# Pressure_Transducers_SCH.net
KiCad netlist of a schematic drawn in Altium Designer
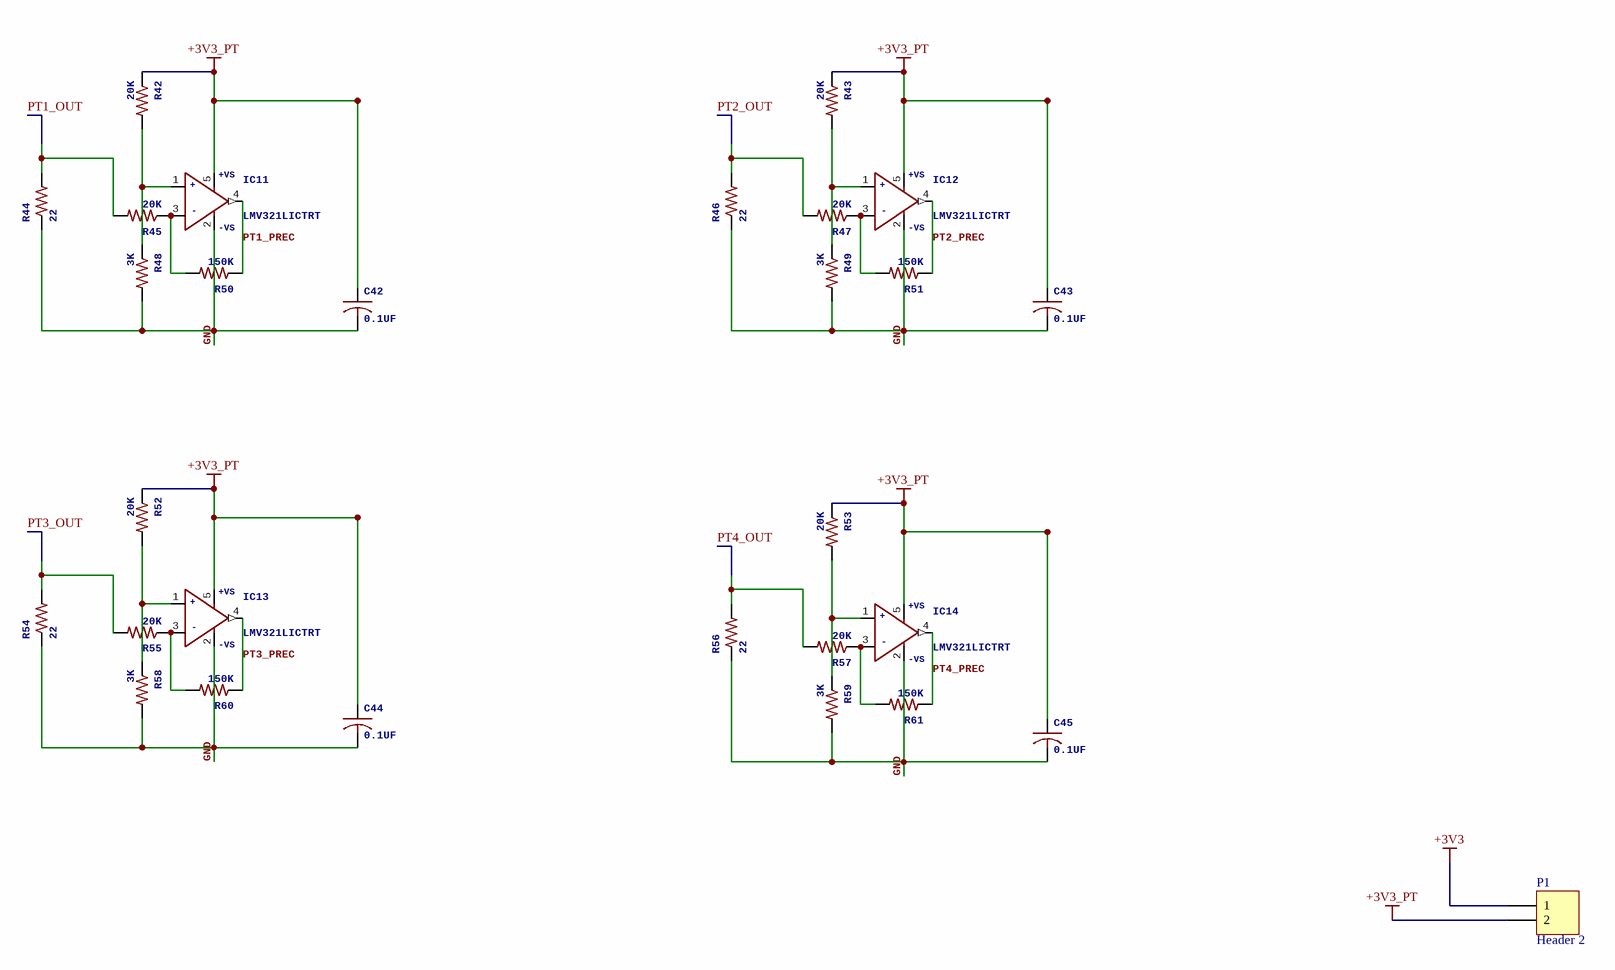
[diagram p0: Pressure_Transducers_SCH.SchDoc]

(export (version "E")
  (design (tool "Eeschema 10.0.6"))
  (components
    (comp (ref "C42")
      (value "0.1UF")
      (footprint "CAPCP2012X06N")
      (description "CAPACITOR, American symbol")
      (libsource (lib "rcl") (part "C-USC0805"))
    )
    (comp (ref "C43")
      (value "0.1UF")
      (footprint "CAPCP2012X06N")
      (description "CAPACITOR, American symbol")
      (libsource (lib "rcl") (part "C-USC0805"))
    )
    (comp (ref "C44")
      (value "0.1UF")
      (footprint "CAPCP2012X06N")
      (description "CAPACITOR, American symbol")
      (libsource (lib "rcl") (part "C-USC0805"))
    )
    (comp (ref "C45")
      (value "0.1UF")
      (footprint "CAPCP2012X06N")
      (description "CAPACITOR, American symbol")
      (libsource (lib "rcl") (part "C-USC0805"))
    )
    (comp (ref "IC11")
      (value "LMV321LICTRT")
      (footprint "SOT95P245X110-5N")
      (fields
        (field (name "MF") "ALTERA CORPORATION")
        (field (name "MPN") "AD8065ARTZ-REEL7")
        (field (name "+") "+")
        (field (name "-") "-")
        (field (name "+VS") "+VS")
        (field (name "-VS") "-VS")
        (field (name "LIBRARYNAME") "st-microelectronics-extra")
      )
      (libsource (lib "st-microelectronics-extra") (part "LMV321LICTRT"))
    )
    (comp (ref "IC12")
      (value "LMV321LICTRT")
      (footprint "SOT95P245X110-5N")
      (fields
        (field (name "MF") "ALTERA CORPORATION")
        (field (name "MPN") "AD8065ARTZ-REEL7")
        (field (name "+") "+")
        (field (name "-") "-")
        (field (name "+VS") "+VS")
        (field (name "-VS") "-VS")
        (field (name "LIBRARYNAME") "st-microelectronics-extra")
      )
      (libsource (lib "st-microelectronics-extra") (part "LMV321LICTRT"))
    )
    (comp (ref "IC13")
      (value "LMV321LICTRT")
      (footprint "SOT95P245X110-5N")
      (fields
        (field (name "MF") "ALTERA CORPORATION")
        (field (name "MPN") "AD8065ARTZ-REEL7")
        (field (name "+") "+")
        (field (name "-") "-")
        (field (name "+VS") "+VS")
        (field (name "-VS") "-VS")
        (field (name "LIBRARYNAME") "st-microelectronics-extra")
      )
      (libsource (lib "st-microelectronics-extra") (part "LMV321LICTRT"))
    )
    (comp (ref "IC14")
      (value "LMV321LICTRT")
      (footprint "SOT95P245X110-5N")
      (fields
        (field (name "MF") "ALTERA CORPORATION")
        (field (name "MPN") "AD8065ARTZ-REEL7")
        (field (name "+") "+")
        (field (name "-") "-")
        (field (name "+VS") "+VS")
        (field (name "-VS") "-VS")
        (field (name "LIBRARYNAME") "st-microelectronics-extra")
      )
      (libsource (lib "st-microelectronics-extra") (part "LMV321LICTRT"))
    )
    (comp (ref "P1")
      (value "Header 2")
      (footprint "HDR1X2")
      (description "Header, 2-Pin")
      (fields (field (name "PUBLISHER") "Altium Limited"))
      (libsource (lib "Miscellaneous Connectors") (part "Header 2"))
    )
    (comp (ref "R42")
      (value "20K")
      (footprint "RESC_0805_2012")
      (description "RESISTOR, American symbol")
      (libsource (lib "rcl") (part "R-US_R0805"))
    )
    (comp (ref "R43")
      (value "20K")
      (footprint "RESC_0805_2012")
      (description "RESISTOR, American symbol")
      (libsource (lib "rcl") (part "R-US_R0805"))
    )
    (comp (ref "R44")
      (value "22")
      (footprint "RESC_0805_2012")
      (description "RESISTOR, American symbol")
      (libsource (lib "rcl") (part "R-US_R0805"))
    )
    (comp (ref "R45")
      (value "20K")
      (footprint "RESC_0805_2012")
      (description "RESISTOR, American symbol")
      (libsource (lib "rcl") (part "R-US_R0805"))
    )
    (comp (ref "R46")
      (value "22")
      (footprint "RESC_0805_2012")
      (description "RESISTOR, American symbol")
      (libsource (lib "rcl") (part "R-US_R0805"))
    )
    (comp (ref "R47")
      (value "20K")
      (footprint "RESC_0805_2012")
      (description "RESISTOR, American symbol")
      (libsource (lib "rcl") (part "R-US_R0805"))
    )
    (comp (ref "R48")
      (value "3K")
      (footprint "RESC_0805_2012")
      (description "RESISTOR, American symbol")
      (libsource (lib "rcl") (part "R-US_R0805"))
    )
    (comp (ref "R49")
      (value "3K")
      (footprint "RESC_0805_2012")
      (description "RESISTOR, American symbol")
      (libsource (lib "rcl") (part "R-US_R0805"))
    )
    (comp (ref "R50")
      (value "150K")
      (footprint "RESC_0805_2012")
      (description "RESISTOR, American symbol")
      (libsource (lib "rcl") (part "R-US_R0805"))
    )
    (comp (ref "R51")
      (value "150K")
      (footprint "RESC_0805_2012")
      (description "RESISTOR, American symbol")
      (libsource (lib "rcl") (part "R-US_R0805"))
    )
    (comp (ref "R52")
      (value "20K")
      (footprint "RESC_0805_2012")
      (description "RESISTOR, American symbol")
      (libsource (lib "rcl") (part "R-US_R0805"))
    )
    (comp (ref "R53")
      (value "20K")
      (footprint "RESC_0805_2012")
      (description "RESISTOR, American symbol")
      (libsource (lib "rcl") (part "R-US_R0805"))
    )
    (comp (ref "R54")
      (value "22")
      (footprint "RESC_0805_2012")
      (description "RESISTOR, American symbol")
      (libsource (lib "rcl") (part "R-US_R0805"))
    )
    (comp (ref "R55")
      (value "20K")
      (footprint "RESC_0805_2012")
      (description "RESISTOR, American symbol")
      (libsource (lib "rcl") (part "R-US_R0805"))
    )
    (comp (ref "R56")
      (value "22")
      (footprint "RESC_0805_2012")
      (description "RESISTOR, American symbol")
      (libsource (lib "rcl") (part "R-US_R0805"))
    )
    (comp (ref "R57")
      (value "20K")
      (footprint "RESC_0805_2012")
      (description "RESISTOR, American symbol")
      (libsource (lib "rcl") (part "R-US_R0805"))
    )
    (comp (ref "R58")
      (value "3K")
      (footprint "RESC_0805_2012")
      (description "RESISTOR, American symbol")
      (libsource (lib "rcl") (part "R-US_R0805"))
    )
    (comp (ref "R59")
      (value "3K")
      (footprint "RESC_0805_2012")
      (description "RESISTOR, American symbol")
      (libsource (lib "rcl") (part "R-US_R0805"))
    )
    (comp (ref "R60")
      (value "150K")
      (footprint "RESC_0805_2012")
      (description "RESISTOR, American symbol")
      (libsource (lib "rcl") (part "R-US_R0805"))
    )
    (comp (ref "R61")
      (value "150K")
      (footprint "RESC_0805_2012")
      (description "RESISTOR, American symbol")
      (libsource (lib "rcl") (part "R-US_R0805"))
    )
  )
  (nets
    (net (code "1") (name "+3V3") (class "Default")
      (node (ref "P1") (pin "1") (pinfunction "1_1") (pintype "passive"))
    )
    (net (code "2") (name "+3V3_PT") (class "Default")
      (node (ref "C42") (pin "1") (pinfunction "1_1") (pintype "passive"))
      (node (ref "C43") (pin "1") (pinfunction "1_1") (pintype "passive"))
      (node (ref "C44") (pin "1") (pinfunction "1_1") (pintype "passive"))
      (node (ref "C45") (pin "1") (pinfunction "1_1") (pintype "passive"))
      (node (ref "IC11") (pin "5") (pinfunction "+VS_5") (pintype "passive"))
      (node (ref "IC12") (pin "5") (pinfunction "+VS_5") (pintype "passive"))
      (node (ref "IC13") (pin "5") (pinfunction "+VS_5") (pintype "passive"))
      (node (ref "IC14") (pin "5") (pinfunction "+VS_5") (pintype "passive"))
      (node (ref "P1") (pin "2") (pinfunction "2_2") (pintype "passive"))
      (node (ref "R42") (pin "1") (pinfunction "1_1") (pintype "passive"))
      (node (ref "R43") (pin "1") (pinfunction "1_1") (pintype "passive"))
      (node (ref "R52") (pin "1") (pinfunction "1_1") (pintype "passive"))
      (node (ref "R53") (pin "1") (pinfunction "1_1") (pintype "passive"))
    )
    (net (code "3") (name "/GND") (class "Default")
      (node (ref "C42") (pin "2") (pinfunction "2_2") (pintype "passive"))
      (node (ref "C43") (pin "2") (pinfunction "2_2") (pintype "passive"))
      (node (ref "C44") (pin "2") (pinfunction "2_2") (pintype "passive"))
      (node (ref "C45") (pin "2") (pinfunction "2_2") (pintype "passive"))
      (node (ref "IC11") (pin "2") (pinfunction "-VS_2") (pintype "passive"))
      (node (ref "IC12") (pin "2") (pinfunction "-VS_2") (pintype "passive"))
      (node (ref "IC13") (pin "2") (pinfunction "-VS_2") (pintype "passive"))
      (node (ref "IC14") (pin "2") (pinfunction "-VS_2") (pintype "passive"))
      (node (ref "R44") (pin "1") (pinfunction "1_1") (pintype "passive"))
      (node (ref "R46") (pin "1") (pinfunction "1_1") (pintype "passive"))
      (node (ref "R48") (pin "2") (pinfunction "2_2") (pintype "passive"))
      (node (ref "R49") (pin "2") (pinfunction "2_2") (pintype "passive"))
      (node (ref "R54") (pin "1") (pinfunction "1_1") (pintype "passive"))
      (node (ref "R56") (pin "1") (pinfunction "1_1") (pintype "passive"))
      (node (ref "R58") (pin "2") (pinfunction "2_2") (pintype "passive"))
      (node (ref "R59") (pin "2") (pinfunction "2_2") (pintype "passive"))
    )
    (net (code "4") (name "/PT1_OUT") (class "Default")
      (node (ref "R44") (pin "2") (pinfunction "2_2") (pintype "passive"))
      (node (ref "R45") (pin "2") (pinfunction "2_2") (pintype "passive"))
    )
    (net (code "5") (name "/PT1_PREC") (class "Default")
      (node (ref "IC11") (pin "4") (pinfunction "OUT_4") (pintype "output"))
      (node (ref "R50") (pin "1") (pinfunction "1_1") (pintype "passive"))
    )
    (net (code "6") (name "/PT2_OUT") (class "Default")
      (node (ref "R46") (pin "2") (pinfunction "2_2") (pintype "passive"))
      (node (ref "R47") (pin "2") (pinfunction "2_2") (pintype "passive"))
    )
    (net (code "7") (name "/PT2_PREC") (class "Default")
      (node (ref "IC12") (pin "4") (pinfunction "OUT_4") (pintype "output"))
      (node (ref "R51") (pin "1") (pinfunction "1_1") (pintype "passive"))
    )
    (net (code "8") (name "/PT3_OUT") (class "Default")
      (node (ref "R54") (pin "2") (pinfunction "2_2") (pintype "passive"))
      (node (ref "R55") (pin "2") (pinfunction "2_2") (pintype "passive"))
    )
    (net (code "9") (name "/PT3_PREC") (class "Default")
      (node (ref "IC13") (pin "4") (pinfunction "OUT_4") (pintype "output"))
      (node (ref "R60") (pin "1") (pinfunction "1_1") (pintype "passive"))
    )
    (net (code "10") (name "/PT4_OUT") (class "Default")
      (node (ref "R56") (pin "2") (pinfunction "2_2") (pintype "passive"))
      (node (ref "R57") (pin "2") (pinfunction "2_2") (pintype "passive"))
    )
    (net (code "11") (name "/PT4_PREC") (class "Default")
      (node (ref "IC14") (pin "4") (pinfunction "OUT_4") (pintype "output"))
      (node (ref "R61") (pin "1") (pinfunction "1_1") (pintype "passive"))
    )
    (net (code "12") (name "Net-(IC11-IN+)") (class "Default")
      (node (ref "IC11") (pin "1") (pinfunction "IN+_1") (pintype "passive"))
      (node (ref "R42") (pin "2") (pinfunction "2_2") (pintype "passive"))
      (node (ref "R48") (pin "1") (pinfunction "1_1") (pintype "passive"))
    )
    (net (code "13") (name "Net-(IC11-IN-)") (class "Default")
      (node (ref "IC11") (pin "3") (pinfunction "IN-_3") (pintype "passive"))
      (node (ref "R45") (pin "1") (pinfunction "1_1") (pintype "passive"))
      (node (ref "R50") (pin "2") (pinfunction "2_2") (pintype "passive"))
    )
    (net (code "14") (name "Net-(IC12-IN+)") (class "Default")
      (node (ref "IC12") (pin "1") (pinfunction "IN+_1") (pintype "passive"))
      (node (ref "R43") (pin "2") (pinfunction "2_2") (pintype "passive"))
      (node (ref "R49") (pin "1") (pinfunction "1_1") (pintype "passive"))
    )
    (net (code "15") (name "Net-(IC12-IN-)") (class "Default")
      (node (ref "IC12") (pin "3") (pinfunction "IN-_3") (pintype "passive"))
      (node (ref "R47") (pin "1") (pinfunction "1_1") (pintype "passive"))
      (node (ref "R51") (pin "2") (pinfunction "2_2") (pintype "passive"))
    )
    (net (code "16") (name "Net-(IC13-IN+)") (class "Default")
      (node (ref "IC13") (pin "1") (pinfunction "IN+_1") (pintype "passive"))
      (node (ref "R52") (pin "2") (pinfunction "2_2") (pintype "passive"))
      (node (ref "R58") (pin "1") (pinfunction "1_1") (pintype "passive"))
    )
    (net (code "17") (name "Net-(IC13-IN-)") (class "Default")
      (node (ref "IC13") (pin "3") (pinfunction "IN-_3") (pintype "passive"))
      (node (ref "R55") (pin "1") (pinfunction "1_1") (pintype "passive"))
      (node (ref "R60") (pin "2") (pinfunction "2_2") (pintype "passive"))
    )
    (net (code "18") (name "Net-(IC14-IN+)") (class "Default")
      (node (ref "IC14") (pin "1") (pinfunction "IN+_1") (pintype "passive"))
      (node (ref "R53") (pin "2") (pinfunction "2_2") (pintype "passive"))
      (node (ref "R59") (pin "1") (pinfunction "1_1") (pintype "passive"))
    )
    (net (code "19") (name "Net-(IC14-IN-)") (class "Default")
      (node (ref "IC14") (pin "3") (pinfunction "IN-_3") (pintype "passive"))
      (node (ref "R57") (pin "1") (pinfunction "1_1") (pintype "passive"))
      (node (ref "R61") (pin "2") (pinfunction "2_2") (pintype "passive"))
    )
  )
)
